# LEDSlave_5.net
KiCad netlist of a schematic drawn in EAGLE
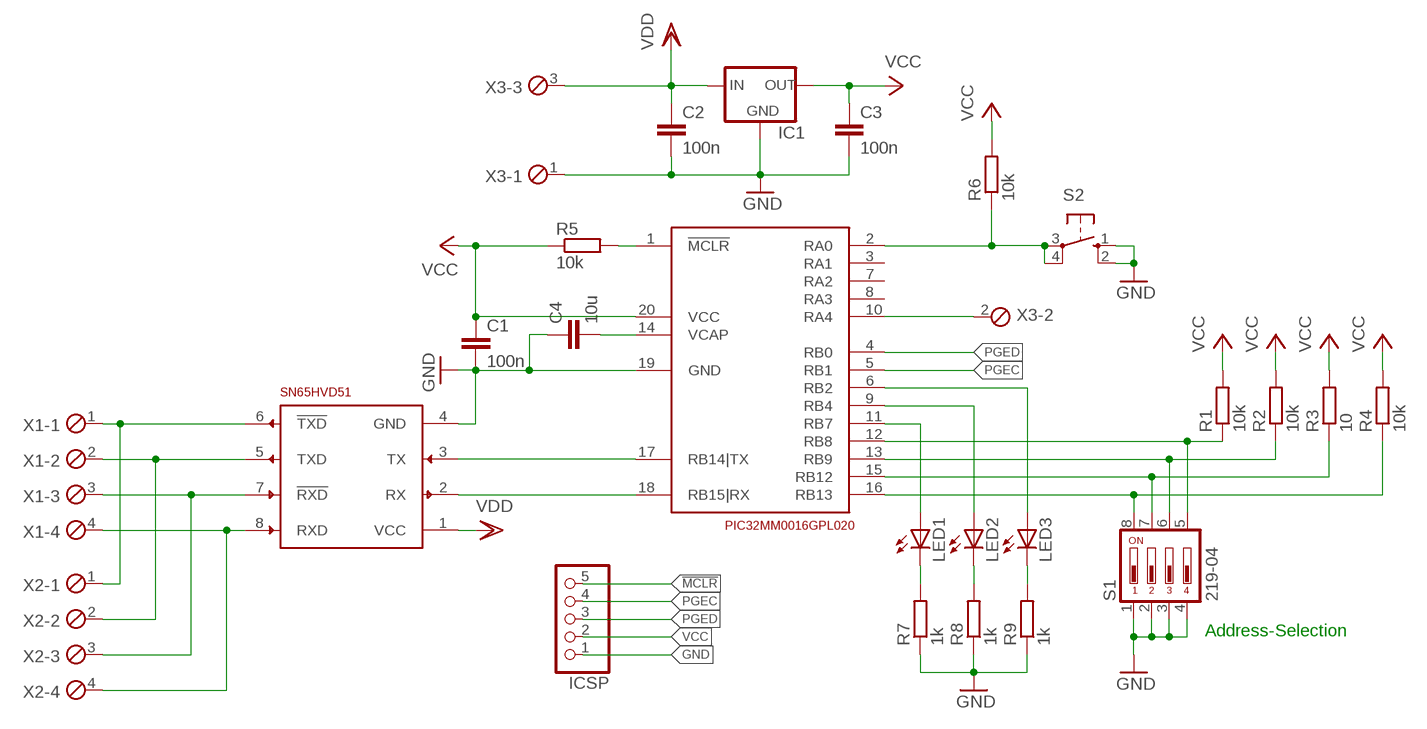
[diagram p0: schematic, sheet 1]

(export (version "E")
  (design (tool "Eeschema 10.0.6"))
  (components
    (comp (ref "C1")
      (value "100n")
      (footprint "eagle-import:C0805")
      (libsource (lib "eagle-import") (part "C-EUC0805"))
    )
    (comp (ref "C2")
      (value "100n")
      (footprint "eagle-import:C0805")
      (libsource (lib "eagle-import") (part "C-EUC0805"))
    )
    (comp (ref "C3")
      (value "100n")
      (footprint "eagle-import:C0805")
      (libsource (lib "eagle-import") (part "C-EUC0805"))
    )
    (comp (ref "C4")
      (value "10u")
      (footprint "eagle-import:C1206")
      (libsource (lib "eagle-import") (part "C-EUC1206"))
    )
    (comp (ref "IC1")
      (value "LP2950CDT-3.3")
      (footprint "eagle-import:DPACK")
      (libsource (lib "eagle-import") (part "LP2950?CDT-3.3"))
    )
    (comp (ref "ICSP")
      (value "PINHD-1X5")
      (footprint "eagle-import:1X05")
      (libsource (lib "eagle-import") (part "PINHD-1X5"))
    )
    (comp (ref "LED1")
      (value "LED3MM")
      (footprint "eagle-import:LED3MM")
      (libsource (lib "eagle-import") (part "LED3MM"))
    )
    (comp (ref "LED2")
      (value "LED3MM")
      (footprint "eagle-import:LED3MM")
      (libsource (lib "eagle-import") (part "LED3MM"))
    )
    (comp (ref "LED3")
      (value "LED3MM")
      (footprint "eagle-import:LED3MM")
      (libsource (lib "eagle-import") (part "LED3MM"))
    )
    (comp (ref "R1")
      (value "10k")
      (footprint "eagle-import:R0805")
      (libsource (lib "eagle-import") (part "R-EU_R0805"))
    )
    (comp (ref "R2")
      (value "10k")
      (footprint "eagle-import:R0805")
      (libsource (lib "eagle-import") (part "R-EU_R0805"))
    )
    (comp (ref "R3")
      (value "10")
      (footprint "eagle-import:R0805")
      (libsource (lib "eagle-import") (part "R-EU_R0805"))
    )
    (comp (ref "R4")
      (value "10k")
      (footprint "eagle-import:R0805")
      (libsource (lib "eagle-import") (part "R-EU_R0805"))
    )
    (comp (ref "R5")
      (value "10k")
      (footprint "eagle-import:R0805")
      (libsource (lib "eagle-import") (part "R-EU_R0805"))
    )
    (comp (ref "R6")
      (value "10k")
      (footprint "eagle-import:R0805")
      (libsource (lib "eagle-import") (part "R-EU_R0805"))
    )
    (comp (ref "R7")
      (value "1k")
      (footprint "eagle-import:R0805")
      (libsource (lib "eagle-import") (part "R-EU_R0805"))
    )
    (comp (ref "R8")
      (value "1k")
      (footprint "eagle-import:R0805")
      (libsource (lib "eagle-import") (part "R-EU_R0805"))
    )
    (comp (ref "R9")
      (value "1k")
      (footprint "eagle-import:R0805")
      (libsource (lib "eagle-import") (part "R-EU_R0805"))
    )
    (comp (ref "S1")
      (value "219-04")
      (footprint "eagle-import:CTS-219-04")
      (libsource (lib "eagle-import") (part "219-04"))
    )
    (comp (ref "S2")
      (value "10-XX")
      (footprint "eagle-import:B3F-10XX")
      (fields (field (name "MPN") "B3F-1000"))
      (libsource (lib "eagle-import") (part "10-XX"))
    )
    (comp (ref "U$1")
      (value "PIC32MM0016GPL020")
      (footprint "eagle-import:SSOP20")
      (libsource (lib "eagle-import") (part "PIC32MM0016GPL020"))
    )
    (comp (ref "U$2")
      (value "SN65HVD51")
      (footprint "eagle-import:SO-08")
      (libsource (lib "eagle-import") (part "SN65HVD51"))
    )
    (comp (ref "X1")
      (value "MPT4")
      (footprint "eagle-import:4POL254")
      (libsource (lib "eagle-import") (part "MPT4"))
    )
    (comp (ref "X2")
      (value "MPT4")
      (footprint "eagle-import:4POL254")
      (libsource (lib "eagle-import") (part "MPT4"))
    )
    (comp (ref "X3")
      (value "MPT3")
      (footprint "eagle-import:3POL254")
      (libsource (lib "eagle-import") (part "MPT3"))
    )
  )
  (nets
    (net (code "1") (name "/~{MCLR}") (class "Default")
      (node (ref "ICSP") (pin "5") (pinfunction "5_5") (pintype "passive"))
      (node (ref "R5") (pin "2") (pinfunction "2_2") (pintype "passive"))
      (node (ref "U$1") (pin "1") (pinfunction "~{MCLR}_1") (pintype "bidirectional"))
    )
    (net (code "2") (name "GND") (class "Default")
      (node (ref "C1") (pin "2") (pinfunction "2_2") (pintype "passive"))
      (node (ref "C2") (pin "2") (pinfunction "2_2") (pintype "passive"))
      (node (ref "C3") (pin "2") (pinfunction "2_2") (pintype "passive"))
      (node (ref "C4") (pin "1") (pinfunction "1_1") (pintype "passive"))
      (node (ref "IC1") (pin "4") (pinfunction "GND_4") (pintype "input"))
      (node (ref "ICSP") (pin "1") (pinfunction "1_1") (pintype "passive"))
      (node (ref "R7") (pin "1") (pinfunction "1_1") (pintype "passive"))
      (node (ref "R8") (pin "1") (pinfunction "1_1") (pintype "passive"))
      (node (ref "R9") (pin "1") (pinfunction "1_1") (pintype "passive"))
      (node (ref "S1") (pin "1") (pinfunction "1_1") (pintype "passive"))
      (node (ref "S1") (pin "2") (pinfunction "2_2") (pintype "passive"))
      (node (ref "S1") (pin "3") (pinfunction "3_3") (pintype "passive"))
      (node (ref "S1") (pin "4") (pinfunction "4_4") (pintype "passive"))
      (node (ref "S2") (pin "1") (pinfunction "S_1") (pintype "passive"))
      (node (ref "S2") (pin "2") (pinfunction "S1_2") (pintype "passive"))
      (node (ref "U$1") (pin "19") (pinfunction "GND_19") (pintype "bidirectional"))
      (node (ref "U$2") (pin "4") (pinfunction "GND_4") (pintype "bidirectional"))
      (node (ref "X3") (pin "1") (pinfunction "1_1") (pintype "passive"))
    )
    (net (code "3") (name "Net-(LED1-C)") (class "Default")
      (node (ref "LED1") (pin "K") (pinfunction "C_K") (pintype "passive"))
      (node (ref "R7") (pin "2") (pinfunction "2_2") (pintype "passive"))
    )
    (net (code "4") (name "Net-(LED2-C)") (class "Default")
      (node (ref "LED2") (pin "K") (pinfunction "C_K") (pintype "passive"))
      (node (ref "R8") (pin "2") (pinfunction "2_2") (pintype "passive"))
    )
    (net (code "5") (name "Net-(LED3-C)") (class "Default")
      (node (ref "LED3") (pin "K") (pinfunction "C_K") (pintype "passive"))
      (node (ref "R9") (pin "2") (pinfunction "2_2") (pintype "passive"))
    )
    (net (code "6") (name "Net-(S2-P)") (class "Default")
      (node (ref "R6") (pin "1") (pinfunction "1_1") (pintype "passive"))
      (node (ref "S2") (pin "3") (pinfunction "P_3") (pintype "passive"))
      (node (ref "S2") (pin "4") (pinfunction "P1_4") (pintype "passive"))
      (node (ref "U$1") (pin "2") (pinfunction "RA0_2") (pintype "bidirectional"))
    )
    (net (code "7") (name "Net-(U$1-RA4)") (class "Default")
      (node (ref "U$1") (pin "10") (pinfunction "RA4_10") (pintype "bidirectional"))
      (node (ref "X3") (pin "2") (pinfunction "1_2") (pintype "passive"))
    )
    (net (code "8") (name "Net-(U$1-RB2)") (class "Default")
      (node (ref "LED3") (pin "A") (pinfunction "A_A") (pintype "passive"))
      (node (ref "U$1") (pin "6") (pinfunction "RB2_6") (pintype "bidirectional"))
    )
    (net (code "9") (name "Net-(U$1-RB4)") (class "Default")
      (node (ref "LED2") (pin "A") (pinfunction "A_A") (pintype "passive"))
      (node (ref "U$1") (pin "9") (pinfunction "RB4_9") (pintype "bidirectional"))
    )
    (net (code "10") (name "Net-(U$1-RB7)") (class "Default")
      (node (ref "LED1") (pin "A") (pinfunction "A_A") (pintype "passive"))
      (node (ref "U$1") (pin "11") (pinfunction "RB7_11") (pintype "bidirectional"))
    )
    (net (code "11") (name "Net-(U$1-RB8)") (class "Default")
      (node (ref "R1") (pin "1") (pinfunction "1_1") (pintype "passive"))
      (node (ref "S1") (pin "5") (pinfunction "5_5") (pintype "passive"))
      (node (ref "U$1") (pin "12") (pinfunction "RB8_12") (pintype "bidirectional"))
    )
    (net (code "12") (name "Net-(U$1-RB9)") (class "Default")
      (node (ref "R2") (pin "1") (pinfunction "1_1") (pintype "passive"))
      (node (ref "S1") (pin "6") (pinfunction "6_6") (pintype "passive"))
      (node (ref "U$1") (pin "13") (pinfunction "RB9_13") (pintype "bidirectional"))
    )
    (net (code "13") (name "Net-(U$1-RB12)") (class "Default")
      (node (ref "R3") (pin "1") (pinfunction "1_1") (pintype "passive"))
      (node (ref "S1") (pin "7") (pinfunction "7_7") (pintype "passive"))
      (node (ref "U$1") (pin "15") (pinfunction "RB12_15") (pintype "bidirectional"))
    )
    (net (code "14") (name "Net-(U$1-RB13)") (class "Default")
      (node (ref "R4") (pin "1") (pinfunction "1_1") (pintype "passive"))
      (node (ref "S1") (pin "8") (pinfunction "8_8") (pintype "passive"))
      (node (ref "U$1") (pin "16") (pinfunction "RB13_16") (pintype "bidirectional"))
    )
    (net (code "15") (name "Net-(U$1-RB14|TX)") (class "Default")
      (node (ref "U$1") (pin "17") (pinfunction "RB14|TX_17") (pintype "bidirectional"))
      (node (ref "U$2") (pin "3") (pinfunction "TX_3") (pintype "bidirectional"))
    )
    (net (code "16") (name "Net-(U$1-RB15|RX)") (class "Default")
      (node (ref "U$1") (pin "18") (pinfunction "RB15|RX_18") (pintype "bidirectional"))
      (node (ref "U$2") (pin "2") (pinfunction "RX_2") (pintype "bidirectional"))
    )
    (net (code "17") (name "Net-(U$1-VCAP)") (class "Default")
      (node (ref "C4") (pin "2") (pinfunction "2_2") (pintype "passive"))
      (node (ref "U$1") (pin "14") (pinfunction "VCAP_14") (pintype "bidirectional"))
    )
    (net (code "18") (name "Net-(U$2-RXD)") (class "Default")
      (node (ref "U$2") (pin "8") (pinfunction "RXD_8") (pintype "bidirectional"))
      (node (ref "X1") (pin "4") (pinfunction "1_4") (pintype "passive"))
      (node (ref "X2") (pin "4") (pinfunction "1_4") (pintype "passive"))
    )
    (net (code "19") (name "Net-(U$2-TXD)") (class "Default")
      (node (ref "U$2") (pin "5") (pinfunction "TXD_5") (pintype "bidirectional"))
      (node (ref "X1") (pin "2") (pinfunction "1_2") (pintype "passive"))
      (node (ref "X2") (pin "2") (pinfunction "1_2") (pintype "passive"))
    )
    (net (code "20") (name "Net-(U$2-~{RXD})") (class "Default")
      (node (ref "U$2") (pin "7") (pinfunction "~{RXD}_7") (pintype "bidirectional"))
      (node (ref "X1") (pin "3") (pinfunction "1_3") (pintype "passive"))
      (node (ref "X2") (pin "3") (pinfunction "1_3") (pintype "passive"))
    )
    (net (code "21") (name "Net-(U$2-~{TXD})") (class "Default")
      (node (ref "U$2") (pin "6") (pinfunction "~{TXD}_6") (pintype "bidirectional"))
      (node (ref "X1") (pin "1") (pinfunction "1_1") (pintype "passive"))
      (node (ref "X2") (pin "1") (pinfunction "1_1") (pintype "passive"))
    )
    (net (code "22") (name "PGEC") (class "Default")
      (node (ref "ICSP") (pin "4") (pinfunction "4_4") (pintype "passive"))
      (node (ref "U$1") (pin "5") (pinfunction "RB1_5") (pintype "bidirectional"))
    )
    (net (code "23") (name "PGED") (class "Default")
      (node (ref "ICSP") (pin "3") (pinfunction "3_3") (pintype "passive"))
      (node (ref "U$1") (pin "4") (pinfunction "RB0_4") (pintype "bidirectional"))
    )
    (net (code "24") (name "VCC") (class "Default")
      (node (ref "C1") (pin "1") (pinfunction "1_1") (pintype "passive"))
      (node (ref "C3") (pin "1") (pinfunction "1_1") (pintype "passive"))
      (node (ref "IC1") (pin "3") (pinfunction "OUT_3") (pintype "passive"))
      (node (ref "ICSP") (pin "2") (pinfunction "2_2") (pintype "passive"))
      (node (ref "R1") (pin "2") (pinfunction "2_2") (pintype "passive"))
      (node (ref "R2") (pin "2") (pinfunction "2_2") (pintype "passive"))
      (node (ref "R3") (pin "2") (pinfunction "2_2") (pintype "passive"))
      (node (ref "R4") (pin "2") (pinfunction "2_2") (pintype "passive"))
      (node (ref "R5") (pin "1") (pinfunction "1_1") (pintype "passive"))
      (node (ref "R6") (pin "2") (pinfunction "2_2") (pintype "passive"))
      (node (ref "U$1") (pin "20") (pinfunction "VCC_20") (pintype "bidirectional"))
    )
    (net (code "25") (name "VDD") (class "Default")
      (node (ref "C2") (pin "1") (pinfunction "1_1") (pintype "passive"))
      (node (ref "IC1") (pin "1") (pinfunction "IN_1") (pintype "input"))
      (node (ref "U$2") (pin "1") (pinfunction "VCC_1") (pintype "bidirectional"))
      (node (ref "X3") (pin "3") (pinfunction "1_3") (pintype "passive"))
    )
    (net (code "26") (name "unconnected-(U$1-RA1-Pad3)") (class "Default")
      (node (ref "U$1") (pin "3") (pinfunction "RA1_3") (pintype "bidirectional"))
    )
    (net (code "27") (name "unconnected-(U$1-RA2-Pad7)") (class "Default")
      (node (ref "U$1") (pin "7") (pinfunction "RA2_7") (pintype "bidirectional"))
    )
    (net (code "28") (name "unconnected-(U$1-RA3-Pad8)") (class "Default")
      (node (ref "U$1") (pin "8") (pinfunction "RA3_8") (pintype "bidirectional"))
    )
  )
)
